# connectivity.net
KiCad netlist of a schematic drawn in Altium Designer
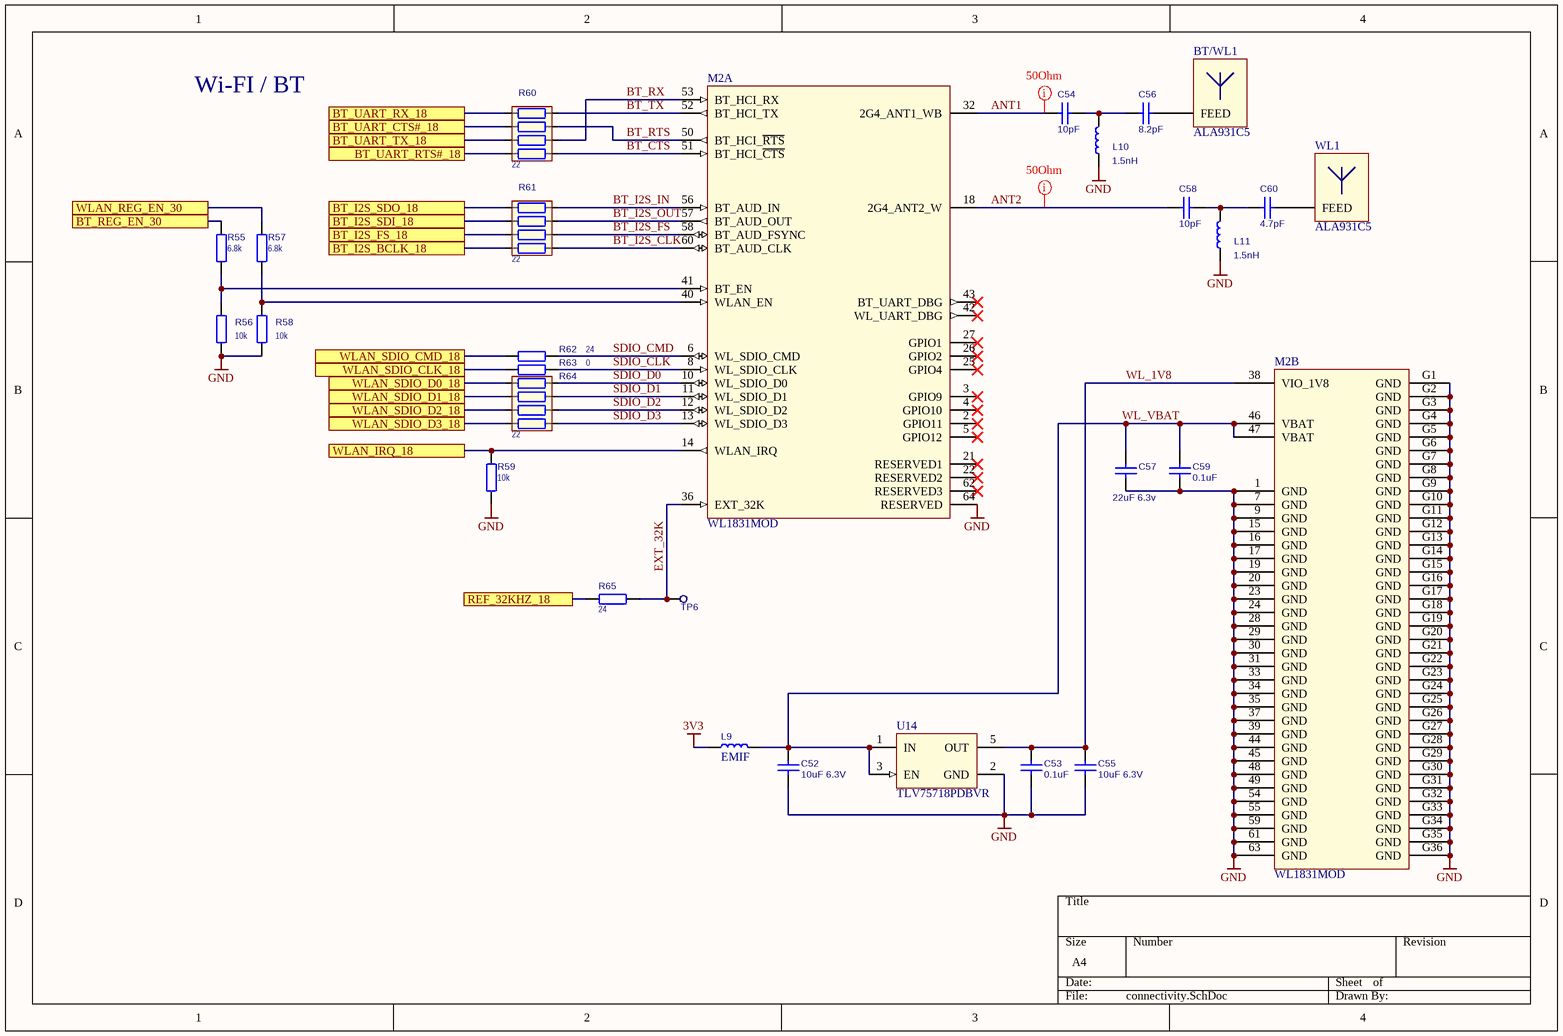
[diagram p0: connectivity.SchDoc]

(export (version "E")
  (design (tool "Eeschema 10.0.6"))
  (components
    (comp (ref "BT/WL1")
      (value "ALA931C5")
      (footprint "9x3x1.2")
      (description "Ceramic chip antenna")
      (libsource (lib "antenna") (part "CHIP-ANT"))
    )
    (comp (ref "C52")
      (value "10uF 6.3V")
      (footprint "Capacitors:C0603")
      (description "CAP_NPOL")
      (fields (field (name "Comment") "CC0603MRX5R5BB106"))
      (libsource (lib "capacitors") (part "CAP_NPOL"))
    )
    (comp (ref "C53")
      (value "0.1uF")
      (footprint "Capacitors:C0603")
      (description "CAP_NPOL")
      (fields (field (name "Comment") "C1608X7R1H104K080AA"))
      (libsource (lib "capacitors") (part "CAP_NPOL"))
    )
    (comp (ref "C54")
      (value "10pF")
      (footprint "C0603")
      (description "CAP_NPOL")
      (fields (field (name "Comment") "CL10C100JB8NNNC"))
      (libsource (lib "capacitors") (part "CAP_NPOL"))
    )
    (comp (ref "C55")
      (value "10uF 6.3V")
      (footprint "Capacitors:C0603")
      (description "CAP_NPOL")
      (fields (field (name "Comment") "CC0603MRX5R5BB106"))
      (libsource (lib "capacitors") (part "CAP_NPOL"))
    )
    (comp (ref "C56")
      (value "8.2pF")
      (footprint "C0603")
      (description "CAP_NPOL")
      (fields (field (name "Comment") "CL10C8R2CB8NNNC"))
      (libsource (lib "capacitors") (part "CAP_NPOL"))
    )
    (comp (ref "C57")
      (value "22uF 6.3v")
      (footprint "C0805")
      (description "CAP_NPOL")
      (fields (field (name "Comment") "CL21A226MQQNNNE"))
      (libsource (lib "capacitors") (part "CAP_NPOL"))
    )
    (comp (ref "C58")
      (value "10pF")
      (footprint "C0603")
      (description "CAP_NPOL")
      (fields (field (name "Comment") "CL10C100JB8NNNC"))
      (libsource (lib "capacitors") (part "CAP_NPOL"))
    )
    (comp (ref "C59")
      (value "0.1uF")
      (footprint "Capacitors:C0603")
      (description "CAP_NPOL")
      (fields (field (name "Comment") "C1608X7R1H104K080AA"))
      (libsource (lib "capacitors") (part "CAP_NPOL"))
    )
    (comp (ref "C60")
      (value "4.7pF")
      (footprint "C0603")
      (description "CAP_NPOL")
      (fields (field (name "Comment") "CC0603CRNPO9BN4R7"))
      (libsource (lib "capacitors") (part "CAP_NPOL"))
    )
    (comp (ref "L9")
      (value "EMIF")
      (footprint "IND0805")
      (description "IND_WO_IRON")
      (fields (field (name "Comment") "BLM21PG221SN1D"))
      (libsource (lib "") (part "IND_WO_IRON_1"))
    )
    (comp (ref "L10")
      (value "1.5nH")
      (footprint "IND0603")
      (description "IND_WO_IRON")
      (libsource (lib "inductors") (part "IND_WO_IRON"))
    )
    (comp (ref "L11")
      (value "1.5nH")
      (footprint "IND0603")
      (description "IND_WO_IRON")
      (libsource (lib "inductors") (part "IND_WO_IRON"))
    )
    (comp (ref "M2")
      (value "WL1831MOD")
      (footprint "E-13.4X13.3-N100_0.75-TOP")
      (libsource (lib "WL18xxMOD") (part "WL18xxMOD"))
    )
    (comp (ref "R55")
      (value "6.8k")
      (footprint "R0603")
      (description "RES")
      (libsource (lib "resistors") (part "RESISTOR"))
    )
    (comp (ref "R56")
      (value "10k")
      (footprint "R0603")
      (description "RES")
      (libsource (lib "resistors") (part "RESISTOR"))
    )
    (comp (ref "R57")
      (value "6.8k")
      (footprint "R0603")
      (description "RES")
      (libsource (lib "resistors") (part "RESISTOR"))
    )
    (comp (ref "R58")
      (value "10k")
      (footprint "R0603")
      (description "RES")
      (libsource (lib "resistors") (part "RESISTOR"))
    )
    (comp (ref "R59")
      (value "10k")
      (footprint "R0603")
      (description "RES")
      (libsource (lib "resistors") (part "RESISTOR"))
    )
    (comp (ref "R60")
      (value "22")
      (footprint "Resistors:R0804X4")
      (description "ARRAY")
      (fields (field (name "Comment") "TC124-JR-0722RL"))
      (libsource (lib "") (part "ARRAY_1"))
    )
    (comp (ref "R61")
      (value "22")
      (footprint "Resistors:R0804X4")
      (description "ARRAY")
      (fields (field (name "Comment") "TC124-JR-0722RL"))
      (libsource (lib "") (part "ARRAY_1"))
    )
    (comp (ref "R62")
      (value "24")
      (footprint "R0603")
      (description "RES")
      (fields (field (name "Comment") "22"))
      (libsource (lib "resistors") (part "RESISTOR"))
    )
    (comp (ref "R63")
      (value "0")
      (footprint "Resistors:R0603")
      (description "RES")
      (libsource (lib "resistors") (part "RESISTOR"))
    )
    (comp (ref "R64")
      (value "22")
      (footprint "Resistors:R0804X4")
      (description "ARRAY")
      (fields (field (name "Comment") "TC124-JR-0722RL"))
      (libsource (lib "resistors") (part "ARRAY"))
    )
    (comp (ref "R65")
      (value "24")
      (footprint "R0603")
      (description "RES")
      (fields (field (name "Comment") "22"))
      (libsource (lib "resistors") (part "RESISTOR"))
    )
    (comp (ref "TP6")
      (value "TEST-POINT")
      (footprint "PAD")
      (description "PCB terminal block")
      (libsource (lib "TestPoint") (part "TEST-POINT"))
    )
    (comp (ref "U14")
      (value "TLV75718PDBVR")
      (footprint "SOT-23-5")
      (description "Capacitor-Free, 300-mA, Low-Dropout Regulator with Foldback Current Limit for Portable Devices")
      (libsource (lib "TLV733P") (part "TLV733P"))
    )
    (comp (ref "WL1")
      (value "ALA931C5")
      (footprint "9x3x1.2")
      (description "Ceramic chip antenna")
      (libsource (lib "antenna") (part "CHIP-ANT"))
    )
  )
  (nets
    (net (code "1") (name "/ANT1") (class "Default")
      (node (ref "C54") (pin "1") (pinfunction "1_1") (pintype "passive"))
      (node (ref "M2") (pin "32") (pinfunction "2G4_ANT1_WB_32") (pintype "passive"))
    )
    (net (code "2") (name "/ANT2") (class "Default")
      (node (ref "C58") (pin "1") (pinfunction "1_1") (pintype "passive"))
      (node (ref "M2") (pin "18") (pinfunction "2G4_ANT2_W_18") (pintype "passive"))
    )
    (net (code "3") (name "/BT_CTS") (class "Default")
      (node (ref "M2") (pin "51") (pinfunction "BT_HCI_~{CTS}_51") (pintype "input"))
      (node (ref "R60") (pin "8") (pinfunction "8_8") (pintype "passive"))
    )
    (net (code "4") (name "/BT_I2S_BCLK_18") (class "Default")
      (node (ref "R61") (pin "7") (pinfunction "7_7") (pintype "passive"))
    )
    (net (code "5") (name "/BT_I2S_CLK") (class "Default")
      (node (ref "M2") (pin "60") (pinfunction "BT_AUD_CLK_60") (pintype "bidirectional"))
      (node (ref "R61") (pin "8") (pinfunction "8_8") (pintype "passive"))
    )
    (net (code "6") (name "/BT_I2S_FS") (class "Default")
      (node (ref "M2") (pin "58") (pinfunction "BT_AUD_FSYNC_58") (pintype "bidirectional"))
      (node (ref "R61") (pin "6") (pinfunction "6_6") (pintype "passive"))
    )
    (net (code "7") (name "/BT_I2S_FS_18") (class "Default")
      (node (ref "R61") (pin "5") (pinfunction "5_5") (pintype "passive"))
    )
    (net (code "8") (name "/BT_I2S_IN") (class "Default")
      (node (ref "M2") (pin "56") (pinfunction "BT_AUD_IN_56") (pintype "input"))
      (node (ref "R61") (pin "2") (pinfunction "2_2") (pintype "passive"))
    )
    (net (code "9") (name "/BT_I2S_OUT") (class "Default")
      (node (ref "M2") (pin "57") (pinfunction "BT_AUD_OUT_57") (pintype "output"))
      (node (ref "R61") (pin "4") (pinfunction "4_4") (pintype "passive"))
    )
    (net (code "10") (name "/BT_I2S_SDI_18") (class "Default")
      (node (ref "R61") (pin "3") (pinfunction "3_3") (pintype "passive"))
    )
    (net (code "11") (name "/BT_I2S_SDO_18") (class "Default")
      (node (ref "R61") (pin "1") (pinfunction "1_1") (pintype "passive"))
    )
    (net (code "12") (name "/BT_REG_EN_30") (class "Default")
      (node (ref "R55") (pin "1") (pinfunction "1_1") (pintype "passive"))
    )
    (net (code "13") (name "/BT_RTS") (class "Default")
      (node (ref "M2") (pin "50") (pinfunction "BT_HCI_~{RTS}_50") (pintype "output"))
      (node (ref "R60") (pin "4") (pinfunction "4_4") (pintype "passive"))
    )
    (net (code "14") (name "/BT_RX") (class "Default")
      (node (ref "M2") (pin "53") (pinfunction "BT_HCI_RX_53") (pintype "input"))
      (node (ref "R60") (pin "6") (pinfunction "6_6") (pintype "passive"))
    )
    (net (code "15") (name "/BT_TX") (class "Default")
      (node (ref "M2") (pin "52") (pinfunction "BT_HCI_TX_52") (pintype "output"))
      (node (ref "R60") (pin "2") (pinfunction "2_2") (pintype "passive"))
    )
    (net (code "16") (name "/BT_UART_CTS#_18") (class "Default")
      (node (ref "R60") (pin "3") (pinfunction "3_3") (pintype "passive"))
    )
    (net (code "17") (name "/BT_UART_RTS#_18") (class "Default")
      (node (ref "R60") (pin "7") (pinfunction "7_7") (pintype "passive"))
    )
    (net (code "18") (name "/BT_UART_RX_18") (class "Default")
      (node (ref "R60") (pin "1") (pinfunction "1_1") (pintype "passive"))
    )
    (net (code "19") (name "/BT_UART_TX_18") (class "Default")
      (node (ref "R60") (pin "5") (pinfunction "5_5") (pintype "passive"))
    )
    (net (code "20") (name "/EXT_32K") (class "Default")
      (node (ref "M2") (pin "36") (pinfunction "EXT_32K_36") (pintype "input"))
      (node (ref "R65") (pin "2") (pinfunction "2_2") (pintype "passive"))
      (node (ref "TP6") (pin "1") (pinfunction "1_1") (pintype "passive"))
    )
    (net (code "21") (name "/REF_32KHZ_18") (class "Default")
      (node (ref "R65") (pin "1") (pinfunction "1_1") (pintype "passive"))
    )
    (net (code "22") (name "/SDIO_CLK") (class "Default")
      (node (ref "M2") (pin "8") (pinfunction "WL_SDIO_CLK_8") (pintype "input"))
      (node (ref "R63") (pin "1") (pinfunction "1_1") (pintype "passive"))
    )
    (net (code "23") (name "/SDIO_CMD") (class "Default")
      (node (ref "M2") (pin "6") (pinfunction "WL_SDIO_CMD_6") (pintype "bidirectional"))
      (node (ref "R62") (pin "1") (pinfunction "1_1") (pintype "passive"))
    )
    (net (code "24") (name "/SDIO_D0") (class "Default")
      (node (ref "M2") (pin "10") (pinfunction "WL_SDIO_D0_10") (pintype "bidirectional"))
      (node (ref "R64") (pin "1") (pinfunction "1_1") (pintype "passive"))
    )
    (net (code "25") (name "/SDIO_D1") (class "Default")
      (node (ref "M2") (pin "11") (pinfunction "WL_SDIO_D1_11") (pintype "bidirectional"))
      (node (ref "R64") (pin "3") (pinfunction "3_3") (pintype "passive"))
    )
    (net (code "26") (name "/SDIO_D2") (class "Default")
      (node (ref "M2") (pin "12") (pinfunction "WL_SDIO_D2_12") (pintype "bidirectional"))
      (node (ref "R64") (pin "5") (pinfunction "5_5") (pintype "passive"))
    )
    (net (code "27") (name "/SDIO_D3") (class "Default")
      (node (ref "M2") (pin "13") (pinfunction "WL_SDIO_D3_13") (pintype "bidirectional"))
      (node (ref "R64") (pin "7") (pinfunction "7_7") (pintype "passive"))
    )
    (net (code "28") (name "/WLAN_IRQ_18") (class "Default")
      (node (ref "M2") (pin "14") (pinfunction "WLAN_IRQ_14") (pintype "output"))
      (node (ref "R59") (pin "2") (pinfunction "2_2") (pintype "passive"))
    )
    (net (code "29") (name "/WLAN_REG_EN_30") (class "Default")
      (node (ref "R57") (pin "1") (pinfunction "1_1") (pintype "passive"))
    )
    (net (code "30") (name "/WLAN_SDIO_CLK_18") (class "Default")
      (node (ref "R63") (pin "2") (pinfunction "2_2") (pintype "passive"))
    )
    (net (code "31") (name "/WLAN_SDIO_CMD_18") (class "Default")
      (node (ref "R62") (pin "2") (pinfunction "2_2") (pintype "passive"))
    )
    (net (code "32") (name "/WLAN_SDIO_D0_18") (class "Default")
      (node (ref "R64") (pin "2") (pinfunction "2_2") (pintype "passive"))
    )
    (net (code "33") (name "/WLAN_SDIO_D1_18") (class "Default")
      (node (ref "R64") (pin "4") (pinfunction "4_4") (pintype "passive"))
    )
    (net (code "34") (name "/WLAN_SDIO_D2_18") (class "Default")
      (node (ref "R64") (pin "6") (pinfunction "6_6") (pintype "passive"))
    )
    (net (code "35") (name "/WLAN_SDIO_D3_18") (class "Default")
      (node (ref "R64") (pin "8") (pinfunction "8_8") (pintype "passive"))
    )
    (net (code "36") (name "/WL_1V8") (class "Default")
      (node (ref "C53") (pin "1") (pinfunction "1_1") (pintype "passive"))
      (node (ref "C55") (pin "1") (pinfunction "1_1") (pintype "passive"))
      (node (ref "M2") (pin "38") (pinfunction "VIO_1V8_38") (pintype "power_in"))
      (node (ref "U14") (pin "5") (pinfunction "OUT_5") (pintype "power_in"))
    )
    (net (code "37") (name "/WL_VBAT") (class "Default")
      (node (ref "C52") (pin "1") (pinfunction "1_1") (pintype "passive"))
      (node (ref "C57") (pin "2") (pinfunction "2_2") (pintype "passive"))
      (node (ref "C59") (pin "2") (pinfunction "2_2") (pintype "passive"))
      (node (ref "L9") (pin "1") (pintype "passive"))
      (node (ref "M2") (pin "46") (pinfunction "VBAT_46") (pintype "power_in"))
      (node (ref "M2") (pin "47") (pinfunction "VBAT_47") (pintype "power_in"))
      (node (ref "U14") (pin "1") (pinfunction "IN_1") (pintype "power_in"))
      (node (ref "U14") (pin "3") (pinfunction "EN_3") (pintype "input"))
    )
    (net (code "38") (name "3V3") (class "Default") (node (ref "L9") (pin "2") (pintype "passive")))
    (net (code "39") (name "GND") (class "Default")
      (node (ref "C52") (pin "2") (pinfunction "2_2") (pintype "passive"))
      (node (ref "C53") (pin "2") (pinfunction "2_2") (pintype "passive"))
      (node (ref "C55") (pin "2") (pinfunction "2_2") (pintype "passive"))
      (node (ref "C57") (pin "1") (pinfunction "1_1") (pintype "passive"))
      (node (ref "C59") (pin "1") (pinfunction "1_1") (pintype "passive"))
      (node (ref "L10") (pin "1") (pintype "passive"))
      (node (ref "L11") (pin "1") (pintype "passive"))
      (node (ref "M2") (pin "1") (pinfunction "GND_1") (pintype "power_in"))
      (node (ref "M2") (pin "15") (pinfunction "GND_15") (pintype "power_in"))
      (node (ref "M2") (pin "16") (pinfunction "GND_16") (pintype "power_in"))
      (node (ref "M2") (pin "17") (pinfunction "GND_17") (pintype "power_in"))
      (node (ref "M2") (pin "19") (pinfunction "GND_19") (pintype "power_in"))
      (node (ref "M2") (pin "20") (pinfunction "GND_20") (pintype "power_in"))
      (node (ref "M2") (pin "23") (pinfunction "GND_23") (pintype "power_in"))
      (node (ref "M2") (pin "24") (pinfunction "GND_24") (pintype "power_in"))
      (node (ref "M2") (pin "28") (pinfunction "GND_28") (pintype "power_in"))
      (node (ref "M2") (pin "29") (pinfunction "GND_29") (pintype "power_in"))
      (node (ref "M2") (pin "30") (pinfunction "GND_30") (pintype "power_in"))
      (node (ref "M2") (pin "31") (pinfunction "GND_31") (pintype "power_in"))
      (node (ref "M2") (pin "33") (pinfunction "GND_33") (pintype "power_in"))
      (node (ref "M2") (pin "34") (pinfunction "GND_34") (pintype "power_in"))
      (node (ref "M2") (pin "35") (pinfunction "GND_35") (pintype "power_in"))
      (node (ref "M2") (pin "37") (pinfunction "GND_37") (pintype "power_in"))
      (node (ref "M2") (pin "39") (pinfunction "GND_39") (pintype "power_in"))
      (node (ref "M2") (pin "44") (pinfunction "GND_44") (pintype "power_in"))
      (node (ref "M2") (pin "45") (pinfunction "GND_45") (pintype "power_in"))
      (node (ref "M2") (pin "48") (pinfunction "GND_48") (pintype "power_in"))
      (node (ref "M2") (pin "49") (pinfunction "GND_49") (pintype "power_in"))
      (node (ref "M2") (pin "54") (pinfunction "GND_54") (pintype "power_in"))
      (node (ref "M2") (pin "55") (pinfunction "GND_55") (pintype "power_in"))
      (node (ref "M2") (pin "59") (pinfunction "GND_59") (pintype "power_in"))
      (node (ref "M2") (pin "61") (pinfunction "GND_61") (pintype "power_in"))
      (node (ref "M2") (pin "63") (pinfunction "GND_63") (pintype "power_in"))
      (node (ref "M2") (pin "64") (pinfunction "RESERVED_64") (pintype "passive"))
      (node (ref "M2") (pin "7") (pinfunction "GND_7") (pintype "power_in"))
      (node (ref "M2") (pin "9") (pinfunction "GND_9") (pintype "power_in"))
      (node (ref "M2") (pin "G1") (pinfunction "GND_G1") (pintype "power_in"))
      (node (ref "M2") (pin "G10") (pinfunction "GND_G10") (pintype "power_in"))
      (node (ref "M2") (pin "G11") (pinfunction "GND_G11") (pintype "power_in"))
      (node (ref "M2") (pin "G12") (pinfunction "GND_G12") (pintype "power_in"))
      (node (ref "M2") (pin "G13") (pinfunction "GND_G13") (pintype "power_in"))
      (node (ref "M2") (pin "G14") (pinfunction "GND_G14") (pintype "power_in"))
      (node (ref "M2") (pin "G15") (pinfunction "GND_G15") (pintype "power_in"))
      (node (ref "M2") (pin "G16") (pinfunction "GND_G16") (pintype "power_in"))
      (node (ref "M2") (pin "G17") (pinfunction "GND_G17") (pintype "power_in"))
      (node (ref "M2") (pin "G18") (pinfunction "GND_G18") (pintype "power_in"))
      (node (ref "M2") (pin "G19") (pinfunction "GND_G19") (pintype "power_in"))
      (node (ref "M2") (pin "G2") (pinfunction "GND_G2") (pintype "power_in"))
      (node (ref "M2") (pin "G20") (pinfunction "GND_G20") (pintype "power_in"))
      (node (ref "M2") (pin "G21") (pinfunction "GND_G21") (pintype "power_in"))
      (node (ref "M2") (pin "G22") (pinfunction "GND_G22") (pintype "power_in"))
      (node (ref "M2") (pin "G23") (pinfunction "GND_G23") (pintype "power_in"))
      (node (ref "M2") (pin "G24") (pinfunction "GND_G24") (pintype "power_in"))
      (node (ref "M2") (pin "G25") (pinfunction "GND_G25") (pintype "power_in"))
      (node (ref "M2") (pin "G26") (pinfunction "GND_G26") (pintype "power_in"))
      (node (ref "M2") (pin "G27") (pinfunction "GND_G27") (pintype "power_in"))
      (node (ref "M2") (pin "G28") (pinfunction "GND_G28") (pintype "power_in"))
      (node (ref "M2") (pin "G29") (pinfunction "GND_G29") (pintype "power_in"))
      (node (ref "M2") (pin "G3") (pinfunction "GND_G3") (pintype "power_in"))
      (node (ref "M2") (pin "G30") (pinfunction "GND_G30") (pintype "power_in"))
      (node (ref "M2") (pin "G31") (pinfunction "GND_G31") (pintype "power_in"))
      (node (ref "M2") (pin "G32") (pinfunction "GND_G32") (pintype "power_in"))
      (node (ref "M2") (pin "G33") (pinfunction "GND_G33") (pintype "power_in"))
      (node (ref "M2") (pin "G34") (pinfunction "GND_G34") (pintype "power_in"))
      (node (ref "M2") (pin "G35") (pinfunction "GND_G35") (pintype "power_in"))
      (node (ref "M2") (pin "G36") (pinfunction "GND_G36") (pintype "power_in"))
      (node (ref "M2") (pin "G4") (pinfunction "GND_G4") (pintype "power_in"))
      (node (ref "M2") (pin "G5") (pinfunction "GND_G5") (pintype "power_in"))
      (node (ref "M2") (pin "G6") (pinfunction "GND_G6") (pintype "power_in"))
      (node (ref "M2") (pin "G7") (pinfunction "GND_G7") (pintype "power_in"))
      (node (ref "M2") (pin "G8") (pinfunction "GND_G8") (pintype "power_in"))
      (node (ref "M2") (pin "G9") (pinfunction "GND_G9") (pintype "power_in"))
      (node (ref "R56") (pin "2") (pinfunction "2_2") (pintype "passive"))
      (node (ref "R58") (pin "1") (pinfunction "1_1") (pintype "passive"))
      (node (ref "R59") (pin "1") (pinfunction "1_1") (pintype "passive"))
      (node (ref "U14") (pin "2") (pinfunction "GND_2") (pintype "power_in"))
    )
    (net (code "40") (name "Net-(BT/WL1-FEED)") (class "Default")
      (node (ref "BT/WL1") (pin "1") (pinfunction "FEED_1") (pintype "passive"))
      (node (ref "C56") (pin "2") (pinfunction "2_2") (pintype "passive"))
    )
    (net (code "41") (name "Net-(C54-Pad2)") (class "Default")
      (node (ref "C54") (pin "2") (pinfunction "2_2") (pintype "passive"))
      (node (ref "C56") (pin "1") (pinfunction "1_1") (pintype "passive"))
      (node (ref "L10") (pin "2") (pintype "passive"))
    )
    (net (code "42") (name "Net-(C58-Pad2)") (class "Default")
      (node (ref "C58") (pin "2") (pinfunction "2_2") (pintype "passive"))
      (node (ref "C60") (pin "1") (pinfunction "1_1") (pintype "passive"))
      (node (ref "L11") (pin "2") (pintype "passive"))
    )
    (net (code "43") (name "Net-(M2A-BT_EN)") (class "Default")
      (node (ref "M2") (pin "41") (pinfunction "BT_EN_41") (pintype "input"))
      (node (ref "R55") (pin "2") (pinfunction "2_2") (pintype "passive"))
      (node (ref "R56") (pin "1") (pinfunction "1_1") (pintype "passive"))
    )
    (net (code "44") (name "Net-(M2A-WLAN_EN)") (class "Default")
      (node (ref "M2") (pin "40") (pinfunction "WLAN_EN_40") (pintype "input"))
      (node (ref "R57") (pin "2") (pinfunction "2_2") (pintype "passive"))
      (node (ref "R58") (pin "2") (pinfunction "2_2") (pintype "passive"))
    )
    (net (code "45") (name "Net-(WL1-FEED)") (class "Default")
      (node (ref "C60") (pin "2") (pinfunction "2_2") (pintype "passive"))
      (node (ref "WL1") (pin "1") (pinfunction "FEED_1") (pintype "passive"))
    )
    (net (code "46") (name "unconnected-(M2A-BT_UART_DBG-Pad43)") (class "Default")
      (node (ref "M2") (pin "43") (pinfunction "BT_UART_DBG_43") (pintype "output+no_connect"))
    )
    (net (code "47") (name "unconnected-(M2A-GPIO1-Pad27)") (class "Default")
      (node (ref "M2") (pin "27") (pinfunction "GPIO1_27") (pintype "passive+no_connect"))
    )
    (net (code "48") (name "unconnected-(M2A-GPIO2-Pad26)") (class "Default")
      (node (ref "M2") (pin "26") (pinfunction "GPIO2_26") (pintype "passive+no_connect"))
    )
    (net (code "49") (name "unconnected-(M2A-GPIO4-Pad25)") (class "Default")
      (node (ref "M2") (pin "25") (pinfunction "GPIO4_25") (pintype "passive+no_connect"))
    )
    (net (code "50") (name "unconnected-(M2A-GPIO9-Pad3)") (class "Default")
      (node (ref "M2") (pin "3") (pinfunction "GPIO9_3") (pintype "passive+no_connect"))
    )
    (net (code "51") (name "unconnected-(M2A-GPIO10-Pad4)") (class "Default")
      (node (ref "M2") (pin "4") (pinfunction "GPIO10_4") (pintype "passive+no_connect"))
    )
    (net (code "52") (name "unconnected-(M2A-GPIO11-Pad2)") (class "Default")
      (node (ref "M2") (pin "2") (pinfunction "GPIO11_2") (pintype "passive+no_connect"))
    )
    (net (code "53") (name "unconnected-(M2A-GPIO12-Pad5)") (class "Default")
      (node (ref "M2") (pin "5") (pinfunction "GPIO12_5") (pintype "passive+no_connect"))
    )
    (net (code "54") (name "unconnected-(M2A-RESERVED1-Pad21)") (class "Default")
      (node (ref "M2") (pin "21") (pinfunction "RESERVED1_21") (pintype "passive+no_connect"))
    )
    (net (code "55") (name "unconnected-(M2A-RESERVED2-Pad22)") (class "Default")
      (node (ref "M2") (pin "22") (pinfunction "RESERVED2_22") (pintype "passive+no_connect"))
    )
    (net (code "56") (name "unconnected-(M2A-RESERVED3-Pad62)") (class "Default")
      (node (ref "M2") (pin "62") (pinfunction "RESERVED3_62") (pintype "passive+no_connect"))
    )
    (net (code "57") (name "unconnected-(M2A-WL_UART_DBG-Pad42)") (class "Default")
      (node (ref "M2") (pin "42") (pinfunction "WL_UART_DBG_42") (pintype "output+no_connect"))
    )
  )
)
